# iTag4.net
KiCad netlist of a schematic drawn in Altium Designer
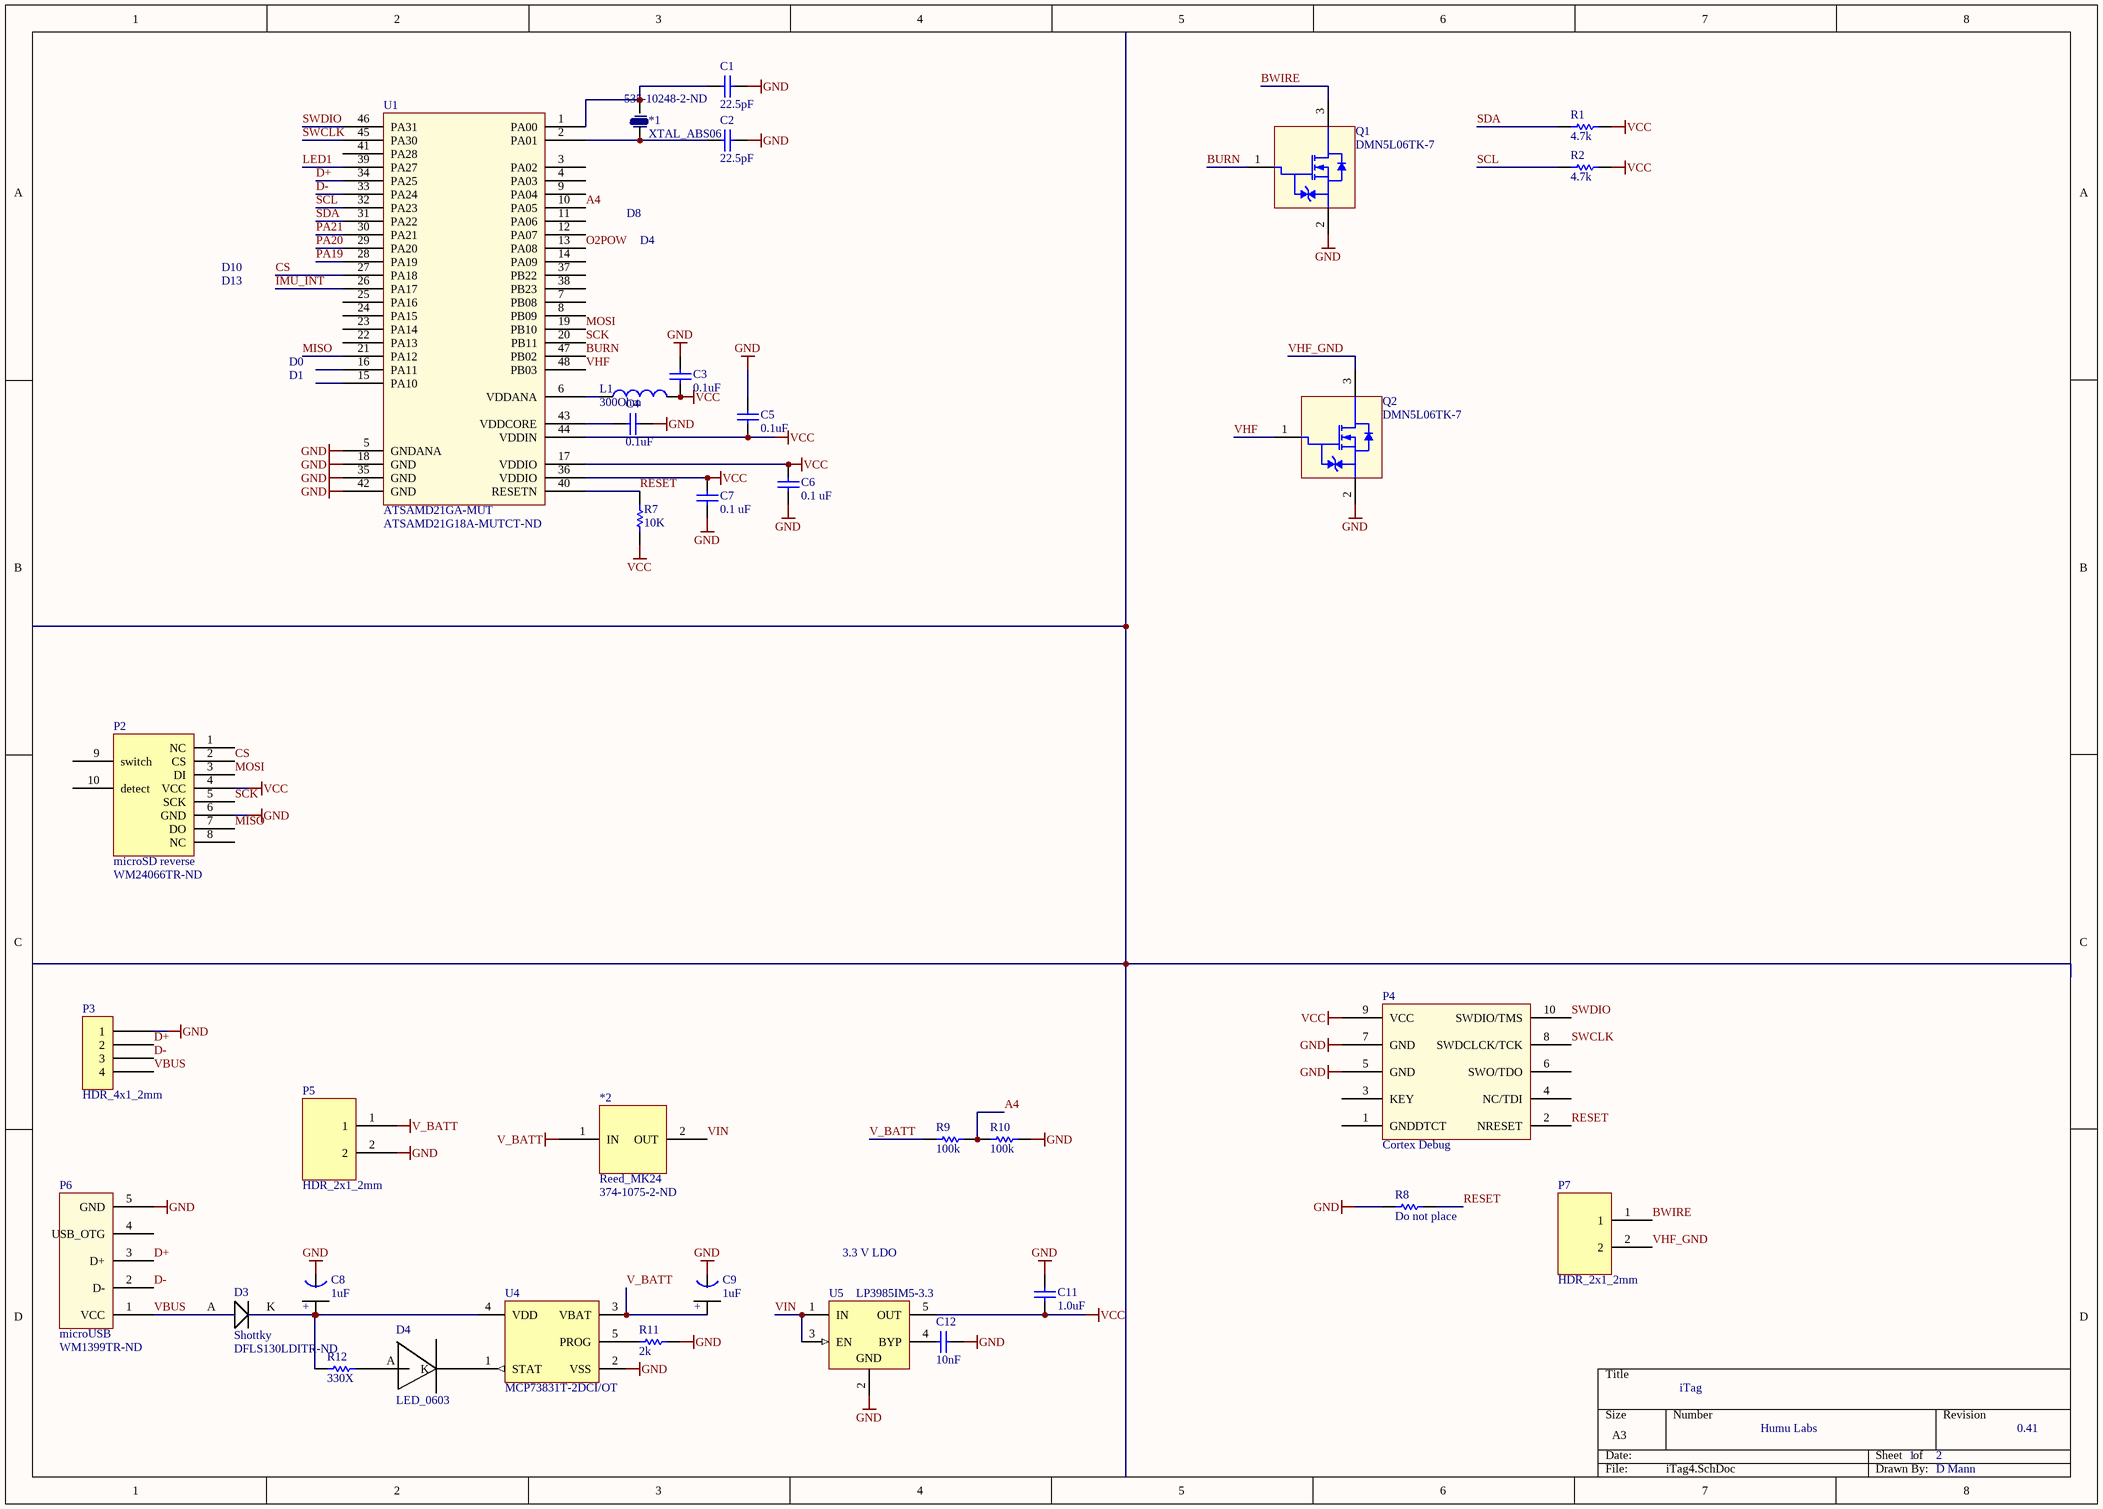
[diagram p0: iTag4.SchDoc]

(export (version "E")
  (design (tool "Eeschema 10.0.6"))
  (components
    (comp (ref "*1")
      (value "XTAL_ABS06")
      (footprint "XTAL-ABS06")
      (fields (field (name "SUPPLIER PART NUMBER 1") "535-10248-2-ND"))
      (libsource (lib "Loggerhead") (part "XTAL_ABS06"))
    )
    (comp (ref "*2")
      (value "Reed_MK24")
      (footprint "Reed MK24-B-3")
      (fields (field (name "SUPPLIER PART NUMBER 1") "374-1075-2-ND"))
      (libsource (lib "Loggerhead") (part "Reed_MK24"))
    )
    (comp (ref "C1")
      (value "22.5pF")
      (footprint "0402")
      (description "Ceramic Chip Capacitor - Standard")
      (fields (field (name "PUBLISHER") "Altium Limited"))
      (libsource (lib "KEMET Chip Capacitor") (part "C0402"))
    )
    (comp (ref "C2")
      (value "22.5pF")
      (footprint "0402")
      (description "Ceramic Chip Capacitor - Standard")
      (fields (field (name "PUBLISHER") "Altium Limited"))
      (libsource (lib "KEMET Chip Capacitor") (part "C0402"))
    )
    (comp (ref "C3")
      (value "0.1uF")
      (footprint "0402")
      (description "Ceramic Chip Capacitor - Standard")
      (fields (field (name "PUBLISHER") "Altium Limited"))
      (libsource (lib "KEMET Chip Capacitor") (part "C0402"))
    )
    (comp (ref "C4")
      (value "0.1uF")
      (footprint "0402")
      (description "Ceramic Chip Capacitor - Standard")
      (fields (field (name "PUBLISHER") "Altium Limited"))
      (libsource (lib "KEMET Chip Capacitor") (part "C0402"))
    )
    (comp (ref "C5")
      (value "0.1uF")
      (footprint "0402")
      (description "Ceramic Chip Capacitor - Standard")
      (fields (field (name "PUBLISHER") "Altium Limited"))
      (libsource (lib "KEMET Chip Capacitor") (part "C0402"))
    )
    (comp (ref "C6")
      (value "0.1 uF")
      (footprint "0402")
      (description "Ceramic Chip Capacitor - Standard")
      (fields (field (name "PUBLISHER") "Altium Limited"))
      (libsource (lib "KEMET Chip Capacitor") (part "C0402"))
    )
    (comp (ref "C7")
      (value "0.1 uF")
      (footprint "0402")
      (description "Ceramic Chip Capacitor - Standard")
      (fields (field (name "PUBLISHER") "Altium Limited"))
      (libsource (lib "KEMET Chip Capacitor") (part "C0402"))
    )
    (comp (ref "C8") (value "1uF") (footprint "Tant0805") (libsource (lib "Loggerhead") (part "Tant0805")))
    (comp (ref "C9") (value "1uF") (footprint "Tant0805") (libsource (lib "Loggerhead") (part "Tant0805")))
    (comp (ref "C11")
      (value "1.0uF")
      (footprint "0402")
      (description "Ceramic Chip Capacitor - Standard")
      (fields (field (name "PUBLISHER") "Altium Limited"))
      (libsource (lib "KEMET Chip Capacitor") (part "C0402"))
    )
    (comp (ref "C12")
      (value "10nF")
      (footprint "0402")
      (description "Ceramic Chip Capacitor - Standard")
      (fields (field (name "PUBLISHER") "Altium Limited"))
      (libsource (lib "KEMET Chip Capacitor") (part "C0402"))
    )
    (comp (ref "D3")
      (value "Shottky")
      (footprint "DFLS130")
      (fields (field (name "SUPPLIER PART NUMBER 1") "DFLS130LDITR-ND"))
      (libsource (lib "Loggerhead") (part "DFLS130"))
    )
    (comp (ref "D4")
      (value "LED_0603")
      (footprint "Diode0603")
      (libsource (lib "Loggerhead") (part "LED_0603"))
    )
    (comp (ref "L1")
      (value "300Ohm")
      (footprint "0805 (M2125) Ferrite")
      (description "Ferrite 25mOhm@DC,  60 Ohm@100MHz")
      (fields
        (field (name "CREATOR AND DATE") "Design Engineer's Name")
        (field (name "FOOTPRINT VERIFIED BY") "*")
        (field (name "SCHEMATIC VERIFIED BY") "*")
        (field (name "VENDOR INFO VERIFIED BY") "*")
      )
      (libsource (lib "Flanery") (part "Ferrite 0805(M2125) 3A"))
    )
    (comp (ref "P2")
      (value "microSD reverse")
      (footprint "miroSD_reverse")
      (fields (field (name "SUPPLIER PART NUMBER 1") "WM24066TR-ND"))
      (libsource (lib "Loggerhead") (part "microSD reverse"))
    )
    (comp (ref "P3")
      (value "HDR_4x1_2mm")
      (footprint "Hdr_4x1_2mm")
      (libsource (lib "Loggerhead") (part "HDR_4x1_2mm"))
    )
    (comp (ref "P4")
      (value "Cortex Debug")
      (footprint "Header_2x5_50mil")
      (libsource (lib "Loggerhead") (part "CortexDebug"))
    )
    (comp (ref "P5")
      (value "HDR_2x1_2mm")
      (footprint "HDR_2x1_2mm")
      (libsource (lib "Loggerhead") (part "HDR_2x1_2mm"))
    )
    (comp (ref "P6")
      (value "microUSB")
      (footprint "microUSB-B")
      (fields (field (name "SUPPLIER PART NUMBER 1") "WM1399TR-ND"))
      (libsource (lib "Loggerhead") (part "microUSB-B"))
    )
    (comp (ref "P7")
      (value "HDR_2x1_2mm")
      (footprint "HDR_2x1_2mm")
      (libsource (lib "Loggerhead") (part "HDR_2x1_2mm"))
    )
    (comp (ref "Q1")
      (value "DMN5L06TK-7")
      (footprint "SOT-523")
      (description "Ultra-low leakage Enhanced MOSFET")
      (fields
        (field (name "CREATOR AND DATE") "Will Flanery 2010-09-02")
        (field (name "FOOTPRINT VERIFIED BY") "*")
        (field (name "SCHEMATIC VERIFIED BY") "*")
        (field (name "VENDOR INFO VERIFIED BY") "*")
      )
      (libsource (lib "Flanery") (part "FET DMN5L06TK-7"))
    )
    (comp (ref "Q2")
      (value "DMN5L06TK-7")
      (footprint "SOT-523")
      (description "Ultra-low leakage Enhanced MOSFET")
      (fields
        (field (name "CREATOR AND DATE") "Will Flanery 2010-09-02")
        (field (name "FOOTPRINT VERIFIED BY") "*")
        (field (name "SCHEMATIC VERIFIED BY") "*")
        (field (name "VENDOR INFO VERIFIED BY") "*")
      )
      (libsource (lib "Flanery") (part "FET DMN5L06TK-7"))
    )
    (comp (ref "R1")
      (value "4.7k")
      (footprint "3-0603")
      (fields (field (name "PUBLISHER") "Altium Limited"))
      (libsource (lib "Panasonic Resistor") (part "ERJ3RK"))
    )
    (comp (ref "R2")
      (value "4.7k")
      (footprint "3-0603")
      (fields (field (name "PUBLISHER") "Altium Limited"))
      (libsource (lib "Panasonic Resistor") (part "ERJ3RK"))
    )
    (comp (ref "R7")
      (value "10K")
      (footprint "3-0603")
      (fields (field (name "PUBLISHER") "Altium Limited"))
      (libsource (lib "Panasonic Resistor") (part "ERJ3RK"))
    )
    (comp (ref "R8")
      (value "Do not place")
      (footprint "3-0603")
      (fields (field (name "PUBLISHER") "Altium Limited"))
      (libsource (lib "Panasonic Resistor") (part "ERJ3RK"))
    )
    (comp (ref "R9")
      (value "100k")
      (footprint "3-0603")
      (fields (field (name "PUBLISHER") "Altium Limited"))
      (libsource (lib "Panasonic Resistor") (part "ERJ3RK"))
    )
    (comp (ref "R10")
      (value "100k")
      (footprint "3-0603")
      (fields (field (name "PUBLISHER") "Altium Limited"))
      (libsource (lib "Panasonic Resistor") (part "ERJ3RK"))
    )
    (comp (ref "R11")
      (value "2k")
      (footprint "3-0603")
      (fields (field (name "PUBLISHER") "Altium Limited"))
      (libsource (lib "Panasonic Resistor") (part "ERJ3RK"))
    )
    (comp (ref "R12")
      (value "330X")
      (footprint "3-0603")
      (fields (field (name "PUBLISHER") "Altium Limited"))
      (libsource (lib "Panasonic Resistor") (part "ERJ3RK"))
    )
    (comp (ref "U1")
      (value "ATSAMD21GA-MUT")
      (footprint "QFN127P600-8N")
      (fields (field (name "SUPPLIER PART NUMBER 1") "ATSAMD21G18A-MUTCT-ND"))
      (libsource (lib "Loggerhead") (part "ATSAMD21G18"))
    )
    (comp (ref "U4")
      (value "MCP73831T-2DCI/OT")
      (footprint "SOT-23-OT5_N")
      (libsource (lib "Microchip Power Management Battery Management") (part "MCP73831T-2DCI/OT"))
    )
    (comp (ref "U5")
      (value "LP3985IM5-3.3")
      (footprint "MF05A_N")
      (description "Micropower, 150mA Low-Noise Ultra Low-Dropout CMOS Voltage Regulator, 5-pin SOT-23")
      (fields
        (field (name "MANUFACTURER") "National Semiconductor")
        (field (name "PUBLISHER") "Altium Limited")
      )
      (libsource (lib "NSC LDO") (part "LP3985IM5-3.3"))
    )
  )
  (nets
    (net (code "1") (name "/A4") (class "Default")
      (node (ref "R10") (pin "2") (pinfunction "2_2") (pintype "passive"))
      (node (ref "R9") (pin "1") (pinfunction "1_1") (pintype "passive"))
      (node (ref "U1") (pin "10") (pinfunction "PA05_10") (pintype "passive"))
    )
    (net (code "2") (name "/BURN") (class "Default")
      (node (ref "Q1") (pin "1") (pinfunction "G_1") (pintype "passive"))
      (node (ref "U1") (pin "47") (pinfunction "PB02_47") (pintype "passive"))
    )
    (net (code "3") (name "/BWIRE") (class "Default")
      (node (ref "P7") (pin "1") (pinfunction "1_1") (pintype "passive"))
      (node (ref "Q1") (pin "3") (pinfunction "D_3") (pintype "passive"))
    )
    (net (code "4") (name "/CS") (class "Default")
      (node (ref "P2") (pin "2") (pinfunction "CS_2") (pintype "passive"))
      (node (ref "U1") (pin "27") (pinfunction "PA18_27") (pintype "passive"))
    )
    (net (code "5") (name "/D+") (class "Default")
      (node (ref "P3") (pin "2") (pinfunction "2_2") (pintype "passive"))
      (node (ref "P6") (pin "3") (pinfunction "D+_3") (pintype "passive"))
      (node (ref "U1") (pin "34") (pinfunction "PA25_34") (pintype "passive"))
    )
    (net (code "6") (name "/D-") (class "Default")
      (node (ref "P3") (pin "3") (pinfunction "3_3") (pintype "passive"))
      (node (ref "P6") (pin "2") (pinfunction "D-_2") (pintype "passive"))
      (node (ref "U1") (pin "33") (pinfunction "PA24_33") (pintype "passive"))
    )
    (net (code "7") (name "/IMU_INT") (class "Default")
      (node (ref "U1") (pin "26") (pinfunction "PA17_26") (pintype "passive"))
    )
    (net (code "8") (name "/LED1") (class "Default")
      (node (ref "U1") (pin "39") (pinfunction "PA27_39") (pintype "passive"))
    )
    (net (code "9") (name "/MISO") (class "Default")
      (node (ref "P2") (pin "7") (pinfunction "DO_7") (pintype "passive"))
      (node (ref "U1") (pin "21") (pinfunction "PA12_21") (pintype "passive"))
    )
    (net (code "10") (name "/MOSI") (class "Default")
      (node (ref "P2") (pin "3") (pinfunction "DI_3") (pintype "passive"))
      (node (ref "U1") (pin "19") (pinfunction "PB10_19") (pintype "passive"))
    )
    (net (code "11") (name "/O2POW") (class "Default")
      (node (ref "U1") (pin "13") (pinfunction "PA08_13") (pintype "passive"))
    )
    (net (code "12") (name "/PA19") (class "Default")
      (node (ref "U1") (pin "28") (pinfunction "PA19_28") (pintype "passive"))
    )
    (net (code "13") (name "/PA20") (class "Default")
      (node (ref "U1") (pin "29") (pinfunction "PA20_29") (pintype "passive"))
    )
    (net (code "14") (name "/PA21") (class "Default")
      (node (ref "U1") (pin "30") (pinfunction "PA21_30") (pintype "passive"))
    )
    (net (code "15") (name "/RESET") (class "Default")
      (node (ref "P4") (pin "2") (pinfunction "NRESET_2") (pintype "passive"))
      (node (ref "R7") (pin "2") (pinfunction "2_2") (pintype "passive"))
      (node (ref "R8") (pin "1") (pinfunction "1_1") (pintype "passive"))
      (node (ref "U1") (pin "40") (pinfunction "RESETN_40") (pintype "passive"))
    )
    (net (code "16") (name "/SCK") (class "Default")
      (node (ref "P2") (pin "5") (pinfunction "SCK_5") (pintype "passive"))
      (node (ref "U1") (pin "20") (pinfunction "PB11_20") (pintype "passive"))
    )
    (net (code "17") (name "/SCL") (class "Default")
      (node (ref "R2") (pin "1") (pinfunction "1_1") (pintype "passive"))
      (node (ref "U1") (pin "32") (pinfunction "PA23_32") (pintype "passive"))
    )
    (net (code "18") (name "/SDA") (class "Default")
      (node (ref "R1") (pin "2") (pinfunction "2_2") (pintype "passive"))
      (node (ref "U1") (pin "31") (pinfunction "PA22_31") (pintype "passive"))
    )
    (net (code "19") (name "/SWCLK") (class "Default")
      (node (ref "P4") (pin "8") (pinfunction "SWDCLCK/TCK_8") (pintype "passive"))
      (node (ref "U1") (pin "45") (pinfunction "PA30_45") (pintype "passive"))
    )
    (net (code "20") (name "/SWDIO") (class "Default")
      (node (ref "P4") (pin "10") (pinfunction "SWDIO/TMS_10") (pintype "passive"))
      (node (ref "U1") (pin "46") (pinfunction "PA31_46") (pintype "passive"))
    )
    (net (code "21") (name "/VBUS") (class "Default")
      (node (ref "D3") (pin "A") (pintype "passive"))
      (node (ref "P3") (pin "4") (pinfunction "4_4") (pintype "passive"))
      (node (ref "P6") (pin "1") (pinfunction "VCC_1") (pintype "passive"))
    )
    (net (code "22") (name "/VHF") (class "Default")
      (node (ref "Q2") (pin "1") (pinfunction "G_1") (pintype "passive"))
      (node (ref "U1") (pin "48") (pinfunction "PB03_48") (pintype "passive"))
    )
    (net (code "23") (name "/VHF_GND") (class "Default")
      (node (ref "P7") (pin "2") (pinfunction "2_2") (pintype "passive"))
      (node (ref "Q2") (pin "3") (pinfunction "D_3") (pintype "passive"))
    )
    (net (code "24") (name "/VIN") (class "Default")
      (node (ref "*2") (pin "2") (pinfunction "OUT_2") (pintype "passive"))
      (node (ref "U5") (pin "1") (pinfunction "IN_1") (pintype "power_in"))
      (node (ref "U5") (pin "3") (pinfunction "EN_3") (pintype "input"))
    )
    (net (code "25") (name "GND") (class "Default")
      (node (ref "C1") (pin "1") (pinfunction "1_1") (pintype "passive"))
      (node (ref "C11") (pin "2") (pinfunction "2_2") (pintype "passive"))
      (node (ref "C12") (pin "1") (pinfunction "1_1") (pintype "passive"))
      (node (ref "C2") (pin "1") (pinfunction "1_1") (pintype "passive"))
      (node (ref "C3") (pin "2") (pinfunction "2_2") (pintype "passive"))
      (node (ref "C4") (pin "2") (pinfunction "2_2") (pintype "passive"))
      (node (ref "C5") (pin "2") (pinfunction "2_2") (pintype "passive"))
      (node (ref "C6") (pin "2") (pinfunction "2_2") (pintype "passive"))
      (node (ref "C7") (pin "2") (pinfunction "2_2") (pintype "passive"))
      (node (ref "C8") (pin "1") (pinfunction "GND_1") (pintype "passive"))
      (node (ref "C9") (pin "1") (pinfunction "GND_1") (pintype "passive"))
      (node (ref "P2") (pin "6") (pinfunction "GND_6") (pintype "passive"))
      (node (ref "P3") (pin "1") (pinfunction "1_1") (pintype "passive"))
      (node (ref "P4") (pin "5") (pinfunction "GND_5") (pintype "passive"))
      (node (ref "P4") (pin "7") (pinfunction "GND_7") (pintype "passive"))
      (node (ref "P5") (pin "2") (pinfunction "2_2") (pintype "passive"))
      (node (ref "P6") (pin "5") (pinfunction "GND_5") (pintype "passive"))
      (node (ref "Q1") (pin "2") (pinfunction "S_2") (pintype "passive"))
      (node (ref "Q2") (pin "2") (pinfunction "S_2") (pintype "passive"))
      (node (ref "R10") (pin "1") (pinfunction "1_1") (pintype "passive"))
      (node (ref "R11") (pin "1") (pinfunction "1_1") (pintype "passive"))
      (node (ref "R8") (pin "2") (pinfunction "2_2") (pintype "passive"))
      (node (ref "U1") (pin "18") (pinfunction "GND_18") (pintype "passive"))
      (node (ref "U1") (pin "35") (pinfunction "GND_35") (pintype "passive"))
      (node (ref "U1") (pin "42") (pinfunction "GND_42") (pintype "passive"))
      (node (ref "U1") (pin "5") (pinfunction "GNDANA_5") (pintype "passive"))
      (node (ref "U4") (pin "2") (pinfunction "VSS_2") (pintype "power_in"))
      (node (ref "U5") (pin "2") (pinfunction "GND_2") (pintype "power_in"))
    )
    (net (code "26") (name "Net-(C8-+)") (class "Default")
      (node (ref "C8") (pin "2") (pinfunction "+_2") (pintype "passive"))
      (node (ref "D3") (pin "K") (pintype "passive"))
      (node (ref "R12") (pin "1") (pinfunction "1_1") (pintype "passive"))
      (node (ref "U4") (pin "4") (pinfunction "VDD_4") (pintype "power_in"))
    )
    (net (code "27") (name "Net-(D4-PadA)") (class "Default")
      (node (ref "D4") (pin "A") (pinfunction "A_A") (pintype "passive"))
      (node (ref "R12") (pin "2") (pinfunction "2_2") (pintype "passive"))
    )
    (net (code "28") (name "Net-(U1-PA00)") (class "Default")
      (node (ref "*1") (pin "2") (pinfunction "2_2") (pintype "passive"))
      (node (ref "C1") (pin "2") (pinfunction "2_2") (pintype "passive"))
      (node (ref "U1") (pin "1") (pinfunction "PA00_1") (pintype "passive"))
    )
    (net (code "29") (name "Net-(U1-PA01)") (class "Default")
      (node (ref "*1") (pin "1") (pinfunction "1_1") (pintype "passive"))
      (node (ref "C2") (pin "2") (pinfunction "2_2") (pintype "passive"))
      (node (ref "U1") (pin "2") (pinfunction "PA01_2") (pintype "passive"))
    )
    (net (code "30") (name "Net-(U1-VDDANA)") (class "Default")
      (node (ref "L1") (pin "1") (pinfunction "1_1") (pintype "passive"))
      (node (ref "U1") (pin "6") (pinfunction "VDDANA_6") (pintype "passive"))
    )
    (net (code "31") (name "Net-(U1-VDDCORE)") (class "Default")
      (node (ref "C4") (pin "1") (pinfunction "1_1") (pintype "passive"))
      (node (ref "U1") (pin "43") (pinfunction "VDDCORE_43") (pintype "passive"))
    )
    (net (code "32") (name "Net-(U4-PROG)") (class "Default")
      (node (ref "R11") (pin "2") (pinfunction "2_2") (pintype "passive"))
      (node (ref "U4") (pin "5") (pinfunction "PROG_5") (pintype "passive"))
    )
    (net (code "33") (name "Net-(U4-STAT)") (class "Default")
      (node (ref "D4") (pin "K") (pinfunction "K_K") (pintype "passive"))
      (node (ref "U4") (pin "1") (pinfunction "STAT_1") (pintype "output"))
    )
    (net (code "34") (name "VCC") (class "Default")
      (node (ref "C11") (pin "1") (pinfunction "1_1") (pintype "passive"))
      (node (ref "C3") (pin "1") (pinfunction "1_1") (pintype "passive"))
      (node (ref "C5") (pin "1") (pinfunction "1_1") (pintype "passive"))
      (node (ref "C6") (pin "1") (pinfunction "1_1") (pintype "passive"))
      (node (ref "C7") (pin "1") (pinfunction "1_1") (pintype "passive"))
      (node (ref "L1") (pin "2") (pinfunction "2_2") (pintype "passive"))
      (node (ref "P2") (pin "4") (pinfunction "VCC_4") (pintype "passive"))
      (node (ref "P4") (pin "9") (pinfunction "VCC_9") (pintype "passive"))
      (node (ref "R1") (pin "1") (pinfunction "1_1") (pintype "passive"))
      (node (ref "R2") (pin "2") (pinfunction "2_2") (pintype "passive"))
      (node (ref "R7") (pin "1") (pinfunction "1_1") (pintype "passive"))
      (node (ref "U1") (pin "17") (pinfunction "VDDIO_17") (pintype "passive"))
      (node (ref "U1") (pin "36") (pinfunction "VDDIO_36") (pintype "passive"))
      (node (ref "U1") (pin "44") (pinfunction "VDDIN_44") (pintype "passive"))
      (node (ref "U5") (pin "5") (pinfunction "OUT_5") (pintype "power_in"))
    )
    (net (code "35") (name "V_BATT") (class "Default")
      (node (ref "*2") (pin "1") (pinfunction "IN_1") (pintype "passive"))
      (node (ref "C9") (pin "2") (pinfunction "+_2") (pintype "passive"))
      (node (ref "P5") (pin "1") (pinfunction "1_1") (pintype "passive"))
      (node (ref "R9") (pin "2") (pinfunction "2_2") (pintype "passive"))
      (node (ref "U4") (pin "3") (pinfunction "VBAT_3") (pintype "power_in"))
    )
    (net (code "36") (name "unconnected-(C12-Pad2)") (class "Default")
      (node (ref "C12") (pin "2") (pinfunction "2_2") (pintype "passive"))
    )
    (net (code "37") (name "unconnected-(P2-NC-Pad1)") (class "Default")
      (node (ref "P2") (pin "1") (pinfunction "NC_1") (pintype "passive"))
    )
    (net (code "38") (name "unconnected-(P2-NC-Pad8)") (class "Default")
      (node (ref "P2") (pin "8") (pinfunction "NC_8") (pintype "passive"))
    )
    (net (code "39") (name "unconnected-(P2-detect-Pad10)") (class "Default")
      (node (ref "P2") (pin "10") (pinfunction "detect_10") (pintype "passive"))
    )
    (net (code "40") (name "unconnected-(P2-switch-Pad9)") (class "Default")
      (node (ref "P2") (pin "9") (pinfunction "switch_9") (pintype "passive"))
    )
    (net (code "41") (name "unconnected-(P4-GNDDTCT-Pad1)") (class "Default")
      (node (ref "P4") (pin "1") (pinfunction "GNDDTCT_1") (pintype "passive"))
    )
    (net (code "42") (name "unconnected-(P4-KEY-Pad3)") (class "Default")
      (node (ref "P4") (pin "3") (pinfunction "KEY_3") (pintype "passive"))
    )
    (net (code "43") (name "unconnected-(P4-NC{slash}TDI-Pad4)") (class "Default")
      (node (ref "P4") (pin "4") (pinfunction "NC/TDI_4") (pintype "passive"))
    )
    (net (code "44") (name "unconnected-(P4-SWO{slash}TDO-Pad6)") (class "Default")
      (node (ref "P4") (pin "6") (pinfunction "SWO/TDO_6") (pintype "passive"))
    )
    (net (code "45") (name "unconnected-(P6-USB_OTG-Pad4)") (class "Default")
      (node (ref "P6") (pin "4") (pinfunction "USB_OTG_4") (pintype "passive"))
    )
    (net (code "46") (name "unconnected-(U1-PA02-Pad3)") (class "Default")
      (node (ref "U1") (pin "3") (pinfunction "PA02_3") (pintype "passive"))
    )
    (net (code "47") (name "unconnected-(U1-PA03-Pad4)") (class "Default")
      (node (ref "U1") (pin "4") (pinfunction "PA03_4") (pintype "passive"))
    )
    (net (code "48") (name "unconnected-(U1-PA04-Pad9)") (class "Default")
      (node (ref "U1") (pin "9") (pinfunction "PA04_9") (pintype "passive"))
    )
    (net (code "49") (name "unconnected-(U1-PA06-Pad11)") (class "Default")
      (node (ref "U1") (pin "11") (pinfunction "PA06_11") (pintype "passive"))
    )
    (net (code "50") (name "unconnected-(U1-PA07-Pad12)") (class "Default")
      (node (ref "U1") (pin "12") (pinfunction "PA07_12") (pintype "passive"))
    )
    (net (code "51") (name "unconnected-(U1-PA09-Pad14)") (class "Default")
      (node (ref "U1") (pin "14") (pinfunction "PA09_14") (pintype "passive"))
    )
    (net (code "52") (name "unconnected-(U1-PA10-Pad15)") (class "Default")
      (node (ref "U1") (pin "15") (pinfunction "PA10_15") (pintype "passive"))
    )
    (net (code "53") (name "unconnected-(U1-PA11-Pad16)") (class "Default")
      (node (ref "U1") (pin "16") (pinfunction "PA11_16") (pintype "passive"))
    )
    (net (code "54") (name "unconnected-(U1-PA13-Pad22)") (class "Default")
      (node (ref "U1") (pin "22") (pinfunction "PA13_22") (pintype "passive"))
    )
    (net (code "55") (name "unconnected-(U1-PA14-Pad23)") (class "Default")
      (node (ref "U1") (pin "23") (pinfunction "PA14_23") (pintype "passive"))
    )
    (net (code "56") (name "unconnected-(U1-PA15-Pad24)") (class "Default")
      (node (ref "U1") (pin "24") (pinfunction "PA15_24") (pintype "passive"))
    )
    (net (code "57") (name "unconnected-(U1-PA16-Pad25)") (class "Default")
      (node (ref "U1") (pin "25") (pinfunction "PA16_25") (pintype "passive"))
    )
    (net (code "58") (name "unconnected-(U1-PA28-Pad41)") (class "Default")
      (node (ref "U1") (pin "41") (pinfunction "PA28_41") (pintype "passive"))
    )
    (net (code "59") (name "unconnected-(U1-PB08-Pad7)") (class "Default")
      (node (ref "U1") (pin "7") (pinfunction "PB08_7") (pintype "passive"))
    )
    (net (code "60") (name "unconnected-(U1-PB09-Pad8)") (class "Default")
      (node (ref "U1") (pin "8") (pinfunction "PB09_8") (pintype "passive"))
    )
    (net (code "61") (name "unconnected-(U1-PB22-Pad37)") (class "Default")
      (node (ref "U1") (pin "37") (pinfunction "PB22_37") (pintype "passive"))
    )
    (net (code "62") (name "unconnected-(U1-PB23-Pad38)") (class "Default")
      (node (ref "U1") (pin "38") (pinfunction "PB23_38") (pintype "passive"))
    )
    (net (code "63") (name "unconnected-(U5-BYP-Pad4)") (class "Default")
      (node (ref "U5") (pin "4") (pinfunction "BYP_4") (pintype "passive"))
    )
  )
)
